# LEDeep_project.net
KiCad netlist of a schematic drawn in Altium Designer
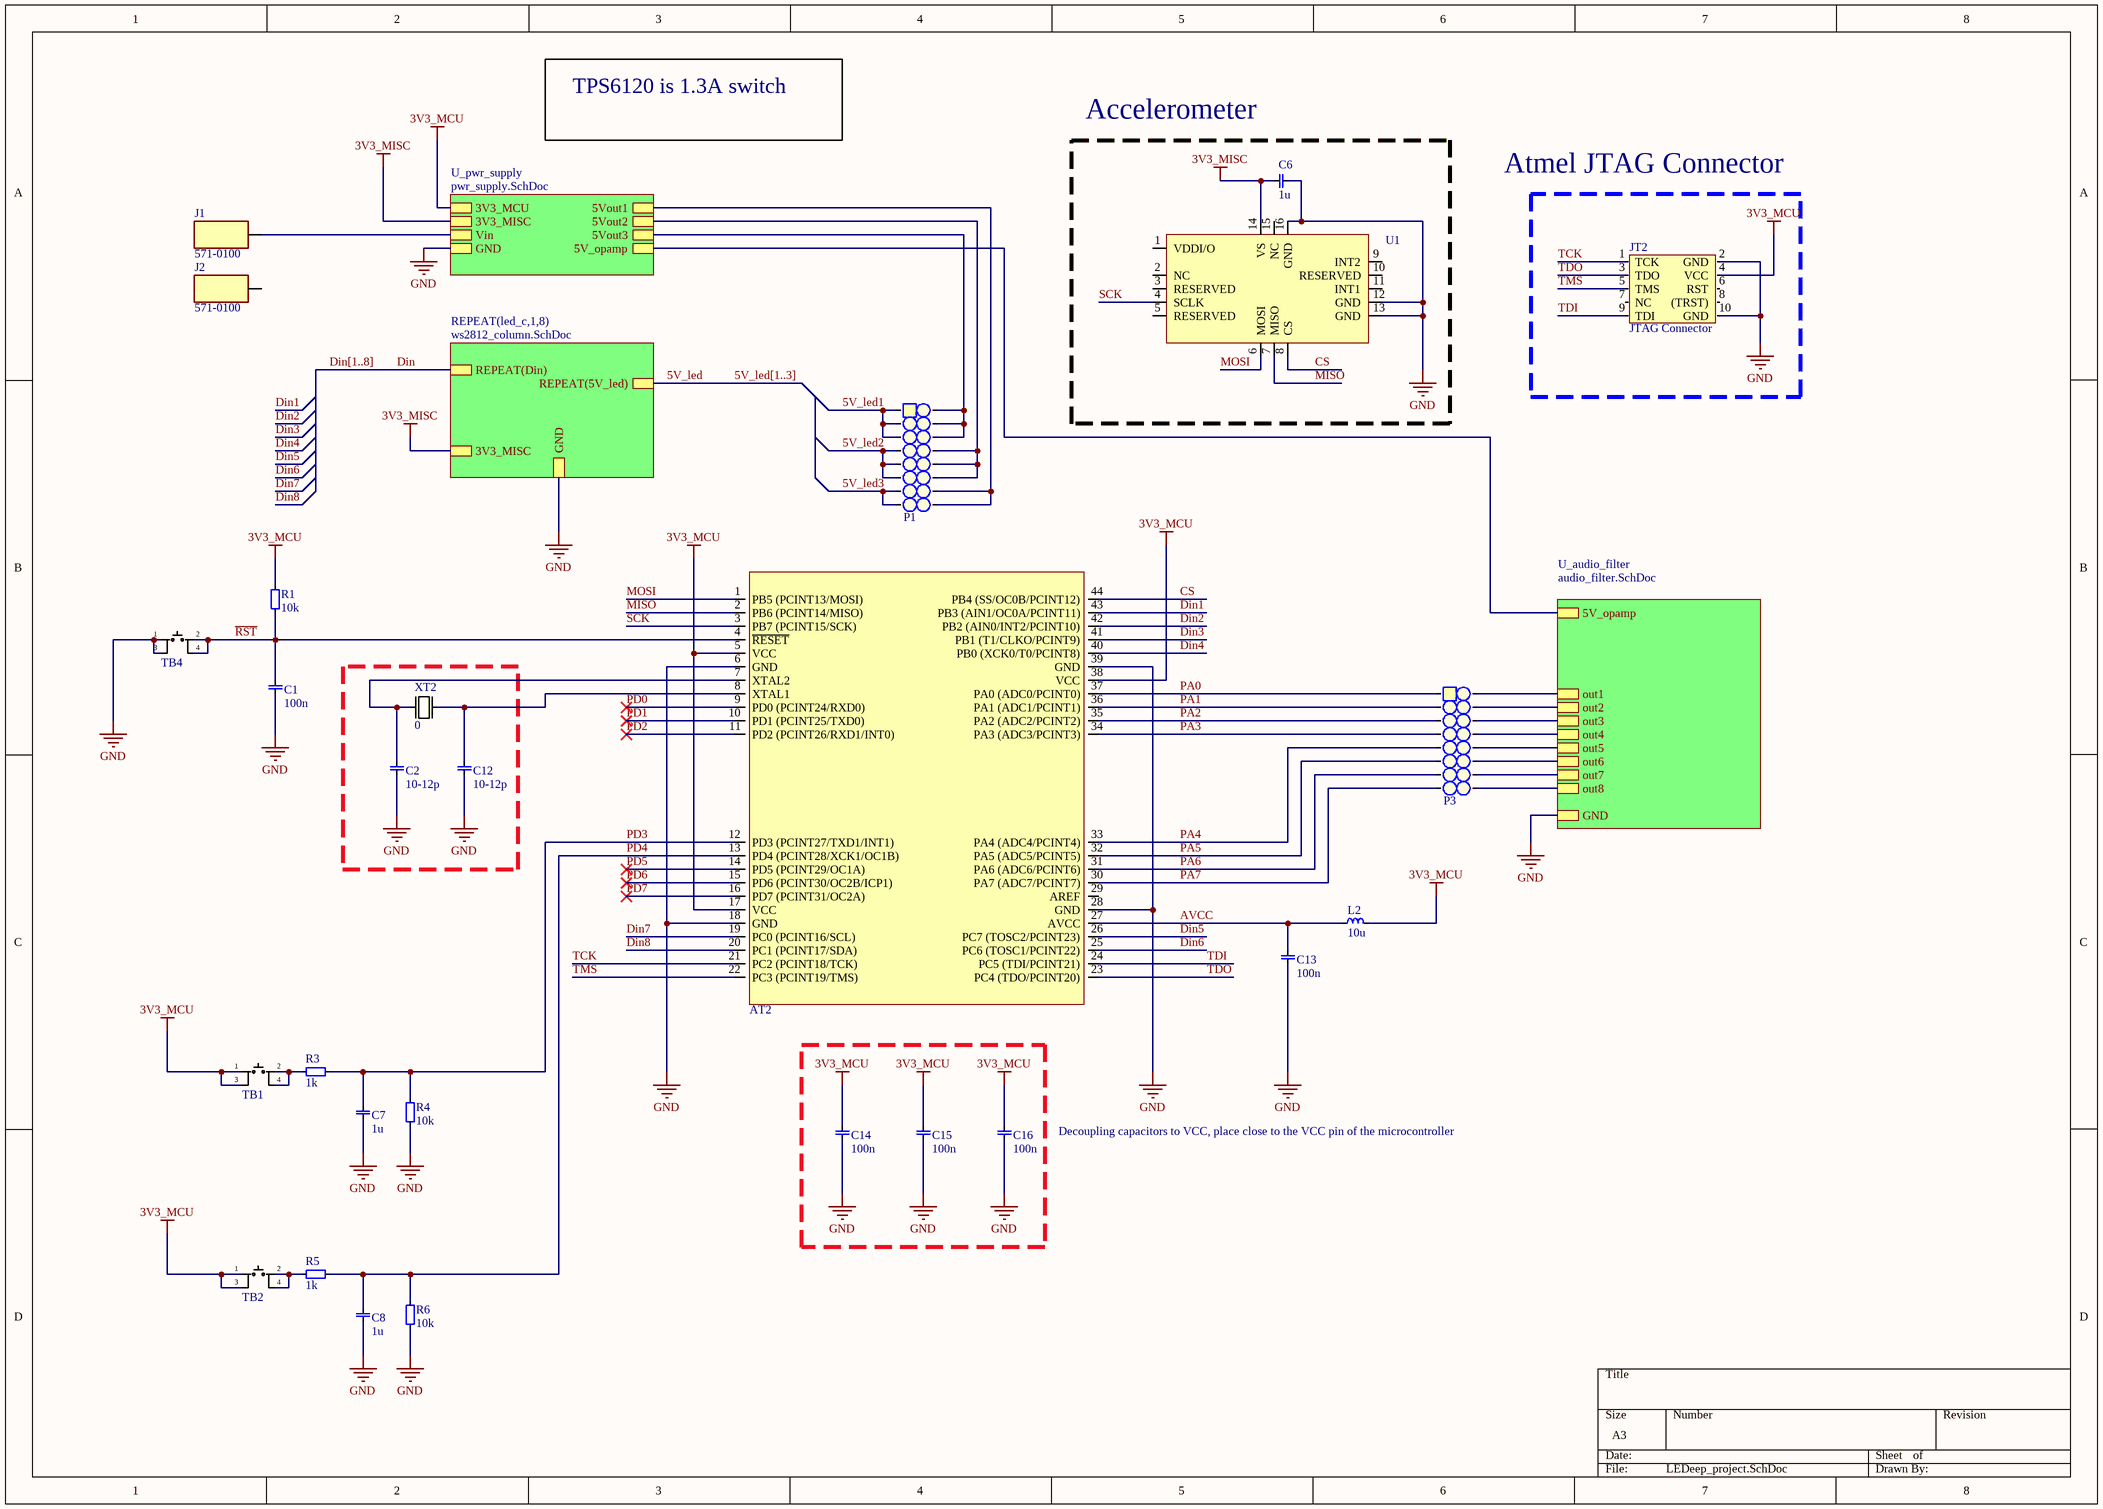
[diagram p0: LEDeep_project.SchDoc]

(export (version "E")
  (design (tool "Eeschema 10.0.6"))
  (components
    (comp (ref "AT2")
      (value "ATmega644PA")
      (footprint "TQFP-44")
      (description "ATmega644PA - Small but big and PicoPower")
      (libsource (lib "eitp15_lab1_lib") (part "ATmega644PA"))
    )
    (comp (ref "C1")
      (value "100n")
      (footprint "1206, capasitor")
      (fields (field (name "Comment") "1206, capacitor"))
      (libsource (lib "eitp15_lab1_lib") (part "1206, capacitor"))
    )
    (comp (ref "C2")
      (value "10-12p")
      (footprint "1206, capasitor")
      (fields (field (name "Comment") "1206, capacitor"))
      (libsource (lib "eitp15_lab1_lib") (part "1206, capacitor"))
    )
    (comp (ref "C6")
      (value "1u")
      (footprint "1206, capasitor")
      (fields (field (name "Comment") "1206, capacitor"))
      (libsource (lib "eitp15_lab1_lib") (part "1206, capacitor"))
    )
    (comp (ref "C7")
      (value "1u")
      (footprint "1206, capasitor")
      (fields (field (name "Comment") "1206, capacitor"))
      (libsource (lib "eitp15_lab1_lib") (part "1206, capacitor"))
    )
    (comp (ref "C8")
      (value "1u")
      (footprint "1206, capasitor")
      (fields (field (name "Comment") "1206, capacitor"))
      (libsource (lib "eitp15_lab1_lib") (part "1206, capacitor"))
    )
    (comp (ref "C12")
      (value "10-12p")
      (footprint "1206, capasitor")
      (fields (field (name "Comment") "1206, capacitor"))
      (libsource (lib "eitp15_lab1_lib") (part "1206, capacitor"))
    )
    (comp (ref "C13")
      (value "100n")
      (footprint "1206, capasitor")
      (fields (field (name "Comment") "1206, capacitor"))
      (libsource (lib "eitp15_lab1_lib") (part "1206, capacitor"))
    )
    (comp (ref "C14")
      (value "100n")
      (footprint "1206, capasitor")
      (fields (field (name "Comment") "1206, capacitor"))
      (libsource (lib "eitp15_lab1_lib") (part "1206, capacitor"))
    )
    (comp (ref "C15")
      (value "100n")
      (footprint "1206, capasitor")
      (fields (field (name "Comment") "1206, capacitor"))
      (libsource (lib "eitp15_lab1_lib") (part "1206, capacitor"))
    )
    (comp (ref "C16")
      (value "100n")
      (footprint "1206, capasitor")
      (fields (field (name "Comment") "1206, capacitor"))
      (libsource (lib "eitp15_lab1_lib") (part "1206, capacitor"))
    )
    (comp (ref "J1")
      (value "571-0100")
      (footprint "Banana Conn VCC")
      (description "Banana Connector 571-0100")
      (fields (field (name "MOUSER PART NUMBER") "164-6218"))
      (libsource (lib "jclib") (part "Banana conn"))
    )
    (comp (ref "J2")
      (value "571-0100")
      (footprint "Banana Conn VCC")
      (description "Banana Connector 571-0100")
      (fields (field (name "MOUSER PART NUMBER") "164-6218"))
      (libsource (lib "") (part "Banana conn_1"))
    )
    (comp (ref "JT2")
      (value "JTAG Connector")
      (footprint "Atmel_JTAG")
      (description "Atmel JTAG Connector")
      (libsource (lib "eitp15_lab1_lib") (part "Atmel JTAG"))
    )
    (comp (ref "L2")
      (value "10u")
      (footprint "1812, coil")
      (fields (field (name "Comment") "Coil"))
      (libsource (lib "eitp15_lab1_lib") (part "Coil"))
    )
    (comp (ref "P1")
      (value "2x8 Pin Header")
      (footprint "2x8 Pin Header")
      (description "2.54 mm")
      (libsource (lib "jclib") (part "2x8 Pin Header"))
    )
    (comp (ref "P3")
      (value "2x8 Pin Header")
      (footprint "2x8 Pin Header")
      (description "2.54 mm")
      (libsource (lib "jclib") (part "2x8 Pin Header"))
    )
    (comp (ref "R1")
      (value "10k")
      (footprint "1206")
      (description "Resistor")
      (fields (field (name "Comment") "1206, resistor"))
      (libsource (lib "eitp15_lab1_lib") (part "1206, resistor"))
    )
    (comp (ref "R3")
      (value "1k")
      (footprint "1206")
      (description "Resistor")
      (fields (field (name "Comment") "1206, resistor"))
      (libsource (lib "eitp15_lab1_lib") (part "1206, resistor"))
    )
    (comp (ref "R4")
      (value "10k")
      (footprint "1206")
      (description "Resistor")
      (fields (field (name "Comment") "1206, resistor"))
      (libsource (lib "eitp15_lab1_lib") (part "1206, resistor"))
    )
    (comp (ref "R5")
      (value "1k")
      (footprint "1206")
      (description "Resistor")
      (fields (field (name "Comment") "1206, resistor"))
      (libsource (lib "eitp15_lab1_lib") (part "1206, resistor"))
    )
    (comp (ref "R6")
      (value "10k")
      (footprint "1206")
      (description "Resistor")
      (fields (field (name "Comment") "1206, resistor"))
      (libsource (lib "eitp15_lab1_lib") (part "1206, resistor"))
    )
    (comp (ref "TB1")
      (value "Tactile Button")
      (footprint "Button smd")
      (description "Tactile Switch Small Low")
      (libsource (lib "eitp15_lab1_lib") (part "Button SMD"))
    )
    (comp (ref "TB2")
      (value "Tactile Button")
      (footprint "Button smd")
      (description "Tactile Switch Small Low")
      (libsource (lib "eitp15_lab1_lib") (part "Button SMD"))
    )
    (comp (ref "TB4")
      (value "Tactile Button")
      (footprint "Button smd")
      (description "Tactile Switch Small Low")
      (libsource (lib "eitp15_lab1_lib") (part "Button SMD"))
    )
    (comp (ref "U1")
      (value "ADXL344")
      (footprint "lag_16_5by3_3x3mm")
      (description "3-Axis, ±2 g/±4 g/±8 g/±16 g Ultralow\r\nPower Digital MEMS Accelerometer")
      (libsource (lib "adxl362") (part "ADXL344"))
    )
    (comp (ref "XT2")
      (value "0")
      (footprint "XTAL_SMD_LP")
      (description "16 MHz, SMD, 5mm x 3,2mm, 30 ppm")
      (fields (field (name "Comment") "XTAL TXC 7A"))
      (libsource (lib "eitp15_lab1_lib") (part "XTAL TXC 7A"))
    )
  )
  (nets
    (net (code "2") (name "/5V_led1") (class "Default")
      (node (ref "P1") (pin "1") (pinfunction "1_1") (pintype "passive"))
      (node (ref "P1") (pin "2") (pinfunction "2_2") (pintype "passive"))
      (node (ref "P1") (pin "3") (pinfunction "3_3") (pintype "passive"))
    )
    (net (code "3") (name "/5V_led2") (class "Default")
      (node (ref "P1") (pin "4") (pinfunction "4_4") (pintype "passive"))
      (node (ref "P1") (pin "5") (pinfunction "5_5") (pintype "passive"))
      (node (ref "P1") (pin "6") (pinfunction "6_6") (pintype "passive"))
    )
    (net (code "4") (name "/5V_led3") (class "Default")
      (node (ref "P1") (pin "7") (pinfunction "7_7") (pintype "passive"))
      (node (ref "P1") (pin "8") (pinfunction "8_8") (pintype "passive"))
    )
    (net (code "7") (name "/5Vout1") (class "Default")
      (node (ref "P1") (pin "10") (pinfunction "10_10") (pintype "passive"))
      (node (ref "P1") (pin "9") (pinfunction "9_9") (pintype "passive"))
    )
    (net (code "8") (name "/5Vout2") (class "Default")
      (node (ref "P1") (pin "11") (pinfunction "11_11") (pintype "passive"))
      (node (ref "P1") (pin "12") (pinfunction "12_12") (pintype "passive"))
      (node (ref "P1") (pin "13") (pinfunction "13_13") (pintype "passive"))
    )
    (net (code "9") (name "/5Vout3") (class "Default")
      (node (ref "P1") (pin "14") (pinfunction "14_14") (pintype "passive"))
      (node (ref "P1") (pin "15") (pinfunction "15_15") (pintype "passive"))
      (node (ref "P1") (pin "16") (pinfunction "16_16") (pintype "passive"))
    )
    (net (code "10") (name "/AVCC") (class "Default")
      (node (ref "AT2") (pin "27") (pinfunction "AVCC_27") (pintype "passive"))
      (node (ref "C13") (pin "1") (pinfunction "1_1") (pintype "passive"))
      (node (ref "L2") (pin "2") (pinfunction "2_2") (pintype "passive"))
    )
    (net (code "11") (name "/CS") (class "Default")
      (node (ref "AT2") (pin "44") (pinfunction "PB4_(SS/OC0B/PCINT12)_44") (pintype "passive"))
      (node (ref "U1") (pin "8") (pinfunction "CS_8") (pintype "passive"))
    )
    (net (code "13") (name "/Din1") (class "Default")
      (node (ref "AT2") (pin "43") (pinfunction "PB3_(AIN1/OC0A/PCINT11)_43") (pintype "passive"))
    )
    (net (code "14") (name "/Din2") (class "Default")
      (node (ref "AT2") (pin "42") (pinfunction "PB2_(AIN0/INT2/PCINT10)_42") (pintype "passive"))
    )
    (net (code "15") (name "/Din3") (class "Default")
      (node (ref "AT2") (pin "41") (pinfunction "PB1_(T1/CLKO/PCINT9)_41") (pintype "passive"))
    )
    (net (code "16") (name "/Din4") (class "Default")
      (node (ref "AT2") (pin "40") (pinfunction "PB0_(XCK0/T0/PCINT8)_40") (pintype "passive"))
    )
    (net (code "17") (name "/Din5") (class "Default")
      (node (ref "AT2") (pin "26") (pinfunction "PC7_(TOSC2/PCINT23)_26") (pintype "passive"))
    )
    (net (code "18") (name "/Din6") (class "Default")
      (node (ref "AT2") (pin "25") (pinfunction "PC6_(TOSC1/PCINT22)_25") (pintype "passive"))
    )
    (net (code "19") (name "/Din7") (class "Default")
      (node (ref "AT2") (pin "19") (pinfunction "PC0_(PCINT16/SCL)_19") (pintype "passive"))
    )
    (net (code "20") (name "/Din8") (class "Default")
      (node (ref "AT2") (pin "20") (pinfunction "PC1_(PCINT17/SDA)_20") (pintype "passive"))
    )
    (net (code "22") (name "/MISO") (class "Default")
      (node (ref "AT2") (pin "2") (pinfunction "PB6_(PCINT14/MISO)_2") (pintype "passive"))
      (node (ref "U1") (pin "7") (pinfunction "MISO_7") (pintype "passive"))
    )
    (net (code "23") (name "/MOSI") (class "Default")
      (node (ref "AT2") (pin "1") (pinfunction "PB5_(PCINT13/MOSI)_1") (pintype "passive"))
      (node (ref "U1") (pin "6") (pinfunction "MOSI_6") (pintype "passive"))
    )
    (net (code "24") (name "/PA0") (class "Default")
      (node (ref "AT2") (pin "37") (pinfunction "PA0_(ADC0/PCINT0)_37") (pintype "passive"))
      (node (ref "P3") (pin "1") (pinfunction "1_1") (pintype "passive"))
    )
    (net (code "25") (name "/PA1") (class "Default")
      (node (ref "AT2") (pin "36") (pinfunction "PA1_(ADC1/PCINT1)_36") (pintype "passive"))
      (node (ref "P3") (pin "2") (pinfunction "2_2") (pintype "passive"))
    )
    (net (code "26") (name "/PA2") (class "Default")
      (node (ref "AT2") (pin "35") (pinfunction "PA2_(ADC2/PCINT2)_35") (pintype "passive"))
      (node (ref "P3") (pin "3") (pinfunction "3_3") (pintype "passive"))
    )
    (net (code "27") (name "/PA3") (class "Default")
      (node (ref "AT2") (pin "34") (pinfunction "PA3_(ADC3/PCINT3)_34") (pintype "passive"))
      (node (ref "P3") (pin "4") (pinfunction "4_4") (pintype "passive"))
    )
    (net (code "28") (name "/PA4") (class "Default")
      (node (ref "AT2") (pin "33") (pinfunction "PA4_(ADC4/PCINT4)_33") (pintype "passive"))
      (node (ref "P3") (pin "5") (pinfunction "5_5") (pintype "passive"))
    )
    (net (code "29") (name "/PA5") (class "Default")
      (node (ref "AT2") (pin "32") (pinfunction "PA5_(ADC5/PCINT5)_32") (pintype "passive"))
      (node (ref "P3") (pin "6") (pinfunction "6_6") (pintype "passive"))
    )
    (net (code "30") (name "/PA6") (class "Default")
      (node (ref "AT2") (pin "31") (pinfunction "PA6_(ADC6/PCINT6)_31") (pintype "passive"))
      (node (ref "P3") (pin "7") (pinfunction "7_7") (pintype "passive"))
    )
    (net (code "31") (name "/PA7") (class "Default")
      (node (ref "AT2") (pin "30") (pinfunction "PA7_(ADC7/PCINT7)_30") (pintype "passive"))
      (node (ref "P3") (pin "8") (pinfunction "8_8") (pintype "passive"))
    )
    (net (code "32") (name "/PD0") (class "Default")
      (node (ref "AT2") (pin "9") (pinfunction "PD0_(PCINT24/RXD0)_9") (pintype "passive+no_connect"))
    )
    (net (code "33") (name "/PD1") (class "Default")
      (node (ref "AT2") (pin "10") (pinfunction "PD1_(PCINT25/TXD0)_10") (pintype "passive+no_connect"))
    )
    (net (code "34") (name "/PD2") (class "Default")
      (node (ref "AT2") (pin "11") (pinfunction "PD2_(PCINT26/RXD1/INT0)_11") (pintype "passive+no_connect"))
    )
    (net (code "35") (name "/PD3") (class "Default")
      (node (ref "AT2") (pin "12") (pinfunction "PD3_(PCINT27/TXD1/INT1)_12") (pintype "passive"))
      (node (ref "C7") (pin "1") (pinfunction "1_1") (pintype "passive"))
      (node (ref "R3") (pin "0") (pinfunction "0_0") (pintype "passive"))
      (node (ref "R4") (pin "0") (pinfunction "0_0") (pintype "passive"))
    )
    (net (code "36") (name "/PD4") (class "Default")
      (node (ref "AT2") (pin "13") (pinfunction "PD4_(PCINT28/XCK1/OC1B)_13") (pintype "passive"))
      (node (ref "C8") (pin "1") (pinfunction "1_1") (pintype "passive"))
      (node (ref "R5") (pin "0") (pinfunction "0_0") (pintype "passive"))
      (node (ref "R6") (pin "0") (pinfunction "0_0") (pintype "passive"))
    )
    (net (code "37") (name "/PD5") (class "Default")
      (node (ref "AT2") (pin "14") (pinfunction "PD5_(PCINT29/OC1A)_14") (pintype "passive+no_connect"))
    )
    (net (code "38") (name "/PD6") (class "Default")
      (node (ref "AT2") (pin "15") (pinfunction "PD6_(PCINT30/OC2B/ICP1)_15") (pintype "passive+no_connect"))
    )
    (net (code "39") (name "/PD7") (class "Default")
      (node (ref "AT2") (pin "16") (pinfunction "PD7_(PCINT31/OC2A)_16") (pintype "passive+no_connect"))
    )
    (net (code "40") (name "/SCK") (class "Default")
      (node (ref "AT2") (pin "3") (pinfunction "PB7_(PCINT15/SCK)_3") (pintype "passive"))
      (node (ref "U1") (pin "4") (pinfunction "SCLK_4") (pintype "passive"))
    )
    (net (code "41") (name "/TCK") (class "Default")
      (node (ref "AT2") (pin "21") (pinfunction "PC2_(PCINT18/TCK)_21") (pintype "passive"))
      (node (ref "JT2") (pin "1") (pinfunction "TCK_1") (pintype "passive"))
    )
    (net (code "42") (name "/TDI") (class "Default")
      (node (ref "AT2") (pin "24") (pinfunction "PC5_(TDI/PCINT21)_24") (pintype "passive"))
      (node (ref "JT2") (pin "9") (pinfunction "TDI_9") (pintype "passive"))
    )
    (net (code "43") (name "/TDO") (class "Default")
      (node (ref "AT2") (pin "23") (pinfunction "PC4_(TDO/PCINT20)_23") (pintype "passive"))
      (node (ref "JT2") (pin "3") (pinfunction "TDO_3") (pintype "passive"))
    )
    (net (code "44") (name "/TMS") (class "Default")
      (node (ref "AT2") (pin "22") (pinfunction "PC3_(PCINT19/TMS)_22") (pintype "passive"))
      (node (ref "JT2") (pin "5") (pinfunction "TMS_5") (pintype "passive"))
    )
    (net (code "45") (name "/Vin") (class "Default")
      (node (ref "J1") (pin "1") (pinfunction "1_1") (pintype "passive"))
    )
    (net (code "46") (name "/out1") (class "Default")
      (node (ref "P3") (pin "16") (pinfunction "16_16") (pintype "passive"))
    )
    (net (code "47") (name "/out2") (class "Default")
      (node (ref "P3") (pin "15") (pinfunction "15_15") (pintype "passive"))
    )
    (net (code "48") (name "/out3") (class "Default")
      (node (ref "P3") (pin "14") (pinfunction "14_14") (pintype "passive"))
    )
    (net (code "49") (name "/out4") (class "Default")
      (node (ref "P3") (pin "13") (pinfunction "13_13") (pintype "passive"))
    )
    (net (code "50") (name "/out5") (class "Default")
      (node (ref "P3") (pin "12") (pinfunction "12_12") (pintype "passive"))
    )
    (net (code "51") (name "/out6") (class "Default")
      (node (ref "P3") (pin "11") (pinfunction "11_11") (pintype "passive"))
    )
    (net (code "52") (name "/out7") (class "Default")
      (node (ref "P3") (pin "10") (pinfunction "10_10") (pintype "passive"))
    )
    (net (code "53") (name "/out8") (class "Default")
      (node (ref "P3") (pin "9") (pinfunction "9_9") (pintype "passive"))
    )
    (net (code "54") (name "/~{RST}") (class "Default")
      (node (ref "AT2") (pin "4") (pinfunction "~{RESET}_4") (pintype "passive"))
      (node (ref "C1") (pin "1") (pinfunction "1_1") (pintype "passive"))
      (node (ref "R1") (pin "1") (pinfunction "1_1") (pintype "passive"))
      (node (ref "TB4") (pin "2") (pinfunction "2_2") (pintype "passive"))
      (node (ref "TB4") (pin "4") (pinfunction "4_4") (pintype "passive"))
    )
    (net (code "55") (name "3V3_MCU") (class "Default")
      (node (ref "AT2") (pin "17") (pinfunction "VCC_17") (pintype "passive"))
      (node (ref "AT2") (pin "38") (pinfunction "VCC_38") (pintype "passive"))
      (node (ref "AT2") (pin "5") (pinfunction "VCC_5") (pintype "passive"))
      (node (ref "C14") (pin "1") (pinfunction "1_1") (pintype "passive"))
      (node (ref "C15") (pin "1") (pinfunction "1_1") (pintype "passive"))
      (node (ref "C16") (pin "1") (pinfunction "1_1") (pintype "passive"))
      (node (ref "JT2") (pin "4") (pinfunction "VCC_4") (pintype "passive"))
      (node (ref "L2") (pin "1") (pinfunction "1_1") (pintype "passive"))
      (node (ref "R1") (pin "0") (pinfunction "0_0") (pintype "passive"))
      (node (ref "TB1") (pin "1") (pinfunction "1_1") (pintype "passive"))
      (node (ref "TB1") (pin "3") (pinfunction "3_3") (pintype "passive"))
      (node (ref "TB2") (pin "1") (pinfunction "1_1") (pintype "passive"))
      (node (ref "TB2") (pin "3") (pinfunction "3_3") (pintype "passive"))
    )
    (net (code "56") (name "3V3_MISC") (class "Default")
      (node (ref "C6") (pin "0") (pinfunction "0_0") (pintype "passive"))
      (node (ref "U1") (pin "14") (pinfunction "VS_14") (pintype "passive"))
    )
    (net (code "57") (name "GND") (class "Default")
      (node (ref "AT2") (pin "18") (pinfunction "GND_18") (pintype "passive"))
      (node (ref "AT2") (pin "28") (pinfunction "GND_28") (pintype "passive"))
      (node (ref "AT2") (pin "39") (pinfunction "GND_39") (pintype "passive"))
      (node (ref "AT2") (pin "6") (pinfunction "GND_6") (pintype "passive"))
      (node (ref "C1") (pin "0") (pinfunction "0_0") (pintype "passive"))
      (node (ref "C12") (pin "0") (pinfunction "0_0") (pintype "passive"))
      (node (ref "C13") (pin "0") (pinfunction "0_0") (pintype "passive"))
      (node (ref "C14") (pin "0") (pinfunction "0_0") (pintype "passive"))
      (node (ref "C15") (pin "0") (pinfunction "0_0") (pintype "passive"))
      (node (ref "C16") (pin "0") (pinfunction "0_0") (pintype "passive"))
      (node (ref "C2") (pin "0") (pinfunction "0_0") (pintype "passive"))
      (node (ref "C6") (pin "1") (pinfunction "1_1") (pintype "passive"))
      (node (ref "C7") (pin "0") (pinfunction "0_0") (pintype "passive"))
      (node (ref "C8") (pin "0") (pinfunction "0_0") (pintype "passive"))
      (node (ref "JT2") (pin "10") (pinfunction "GND_10") (pintype "passive"))
      (node (ref "JT2") (pin "2") (pinfunction "GND_2") (pintype "passive"))
      (node (ref "R4") (pin "1") (pinfunction "1_1") (pintype "passive"))
      (node (ref "R6") (pin "1") (pinfunction "1_1") (pintype "passive"))
      (node (ref "TB4") (pin "1") (pinfunction "1_1") (pintype "passive"))
      (node (ref "TB4") (pin "3") (pinfunction "3_3") (pintype "passive"))
      (node (ref "U1") (pin "12") (pinfunction "GND_12") (pintype "passive"))
      (node (ref "U1") (pin "13") (pinfunction "GND_13") (pintype "passive"))
      (node (ref "U1") (pin "16") (pinfunction "GND_16") (pintype "passive"))
    )
    (net (code "58") (name "Net-(AT2-XTAL1)") (class "Default")
      (node (ref "AT2") (pin "8") (pinfunction "XTAL1_8") (pintype "passive"))
      (node (ref "C12") (pin "1") (pinfunction "1_1") (pintype "passive"))
      (node (ref "XT2") (pin "2") (pinfunction "2_2") (pintype "passive"))
    )
    (net (code "59") (name "Net-(AT2-XTAL2)") (class "Default")
      (node (ref "AT2") (pin "7") (pinfunction "XTAL2_7") (pintype "passive"))
      (node (ref "C2") (pin "1") (pinfunction "1_1") (pintype "passive"))
      (node (ref "XT2") (pin "1") (pinfunction "1_1") (pintype "passive"))
    )
    (net (code "60") (name "Net-(R3-Pad1)") (class "Default")
      (node (ref "R3") (pin "1") (pinfunction "1_1") (pintype "passive"))
      (node (ref "TB1") (pin "2") (pinfunction "2_2") (pintype "passive"))
      (node (ref "TB1") (pin "4") (pinfunction "4_4") (pintype "passive"))
    )
    (net (code "61") (name "Net-(R5-Pad1)") (class "Default")
      (node (ref "R5") (pin "1") (pinfunction "1_1") (pintype "passive"))
      (node (ref "TB2") (pin "2") (pinfunction "2_2") (pintype "passive"))
      (node (ref "TB2") (pin "4") (pinfunction "4_4") (pintype "passive"))
    )
    (net (code "62") (name "unconnected-(AT2-AREF-Pad29)") (class "Default")
      (node (ref "AT2") (pin "29") (pinfunction "AREF_29") (pintype "passive"))
    )
    (net (code "63") (name "unconnected-(J2-Pad1)") (class "Default")
      (node (ref "J2") (pin "1") (pinfunction "1_1") (pintype "passive"))
    )
    (net (code "64") (name "unconnected-(JT2-(TRST)-Pad8)") (class "Default")
      (node (ref "JT2") (pin "8") (pinfunction "(TRST)_8") (pintype "passive"))
    )
    (net (code "65") (name "unconnected-(JT2-NC-Pad7)") (class "Default")
      (node (ref "JT2") (pin "7") (pinfunction "NC_7") (pintype "passive"))
    )
    (net (code "66") (name "unconnected-(JT2-RST-Pad6)") (class "Default")
      (node (ref "JT2") (pin "6") (pinfunction "RST_6") (pintype "passive"))
    )
    (net (code "67") (name "unconnected-(U1-INT1-Pad11)") (class "Default")
      (node (ref "U1") (pin "11") (pinfunction "INT1_11") (pintype "passive"))
    )
    (net (code "68") (name "unconnected-(U1-INT2-Pad9)") (class "Default")
      (node (ref "U1") (pin "9") (pinfunction "INT2_9") (pintype "passive"))
    )
    (net (code "69") (name "unconnected-(U1-NC-Pad2)") (class "Default")
      (node (ref "U1") (pin "2") (pinfunction "NC_2") (pintype "passive"))
    )
    (net (code "70") (name "unconnected-(U1-NC-Pad15)") (class "Default")
      (node (ref "U1") (pin "15") (pinfunction "NC_15") (pintype "passive"))
    )
    (net (code "71") (name "unconnected-(U1-RESERVED-Pad3)") (class "Default")
      (node (ref "U1") (pin "3") (pinfunction "RESERVED_3") (pintype "passive"))
    )
    (net (code "72") (name "unconnected-(U1-RESERVED-Pad5)") (class "Default")
      (node (ref "U1") (pin "5") (pinfunction "RESERVED_5") (pintype "passive"))
    )
    (net (code "73") (name "unconnected-(U1-RESERVED-Pad10)") (class "Default")
      (node (ref "U1") (pin "10") (pinfunction "RESERVED_10") (pintype "passive"))
    )
    (net (code "74") (name "unconnected-(U1-VDDI{slash}O-Pad1)") (class "Default")
      (node (ref "U1") (pin "1") (pinfunction "VDDI/O_1") (pintype "passive"))
    )
  )
)
